# Led.net
KiCad netlist of a schematic drawn in Altium Designer
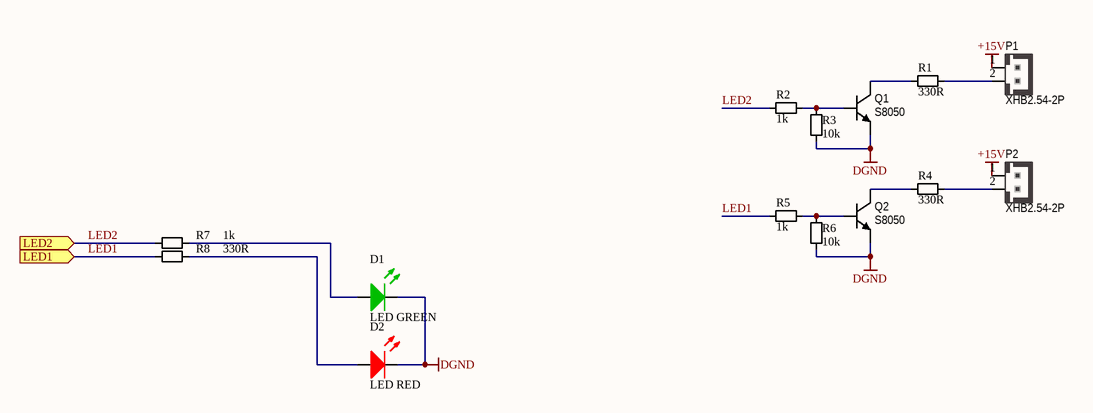
[diagram p0: Led.SchDoc]

(export (version "E")
  (design (tool "Eeschema 10.0.6"))
  (components
    (comp (ref "D1")
      (value "LED GREEN")
      (footprint "GreenBox:0805-LED-G")
      (description "LIGHT EMITTING DIODE 0805 GREEN")
      (fields (field (name "PUBLISHER") "GreenBox"))
      (libsource (lib "Diode_Transistor") (part "D614000000G0"))
    )
    (comp (ref "D2")
      (value "LED RED")
      (footprint "GreenBox:0805-LED-R")
      (description "LIGHT EMITTING DIODE 0805 RED")
      (fields (field (name "PUBLISHER") "GreenBox"))
      (libsource (lib "Diode_Transistor") (part "D614000000R0"))
    )
    (comp (ref "P1")
      (value "XHB2.54-2P")
      (footprint "GreenBox:XH-2")
      (description "Header XHB2.54-2P 2.54mm")
      (fields (field (name "PUBLISHER") "GreenBox"))
      (libsource (lib "Connectors") (part "P6DX02Z25400"))
    )
    (comp (ref "P2")
      (value "XHB2.54-2P")
      (footprint "GreenBox:XH-2")
      (description "Header XHB2.54-2P 2.54mm")
      (fields (field (name "PUBLISHER") "GreenBox"))
      (libsource (lib "Connectors") (part "P6DX02Z25400"))
    )
    (comp (ref "Q1")
      (value "S8050")
      (footprint "GreenBox:SOT-23_N")
      (description "NPN S8050 Icm 0.5A Vcbo 40V")
      (fields (field (name "PUBLISHER") "GreenBox"))
      (libsource (lib "Diode_Transistor") (part "DN42S8050000"))
    )
    (comp (ref "Q2")
      (value "S8050")
      (footprint "GreenBox:SOT-23_N")
      (description "NPN S8050 Icm 0.5A Vcbo 40V")
      (fields (field (name "PUBLISHER") "GreenBox"))
      (libsource (lib "Diode_Transistor") (part "DN42S8050000"))
    )
    (comp (ref "R1")
      (value "330R")
      (footprint "GreenBox:0603-R")
      (description "SMD Resistor 330R 1% 1/10W 0603 100PPM")
      (fields (field (name "Comment") "Res") (field (name "PUBLISHER") "GreenBox"))
      (libsource (lib "Resistor") (part "R11C330RFBF0"))
    )
    (comp (ref "R2")
      (value "1k")
      (footprint "GreenBox:0603-R")
      (description "SMD Resistor 1k 1% 1/10W 0603 100PPM")
      (fields (field (name "Comment") "Res") (field (name "PUBLISHER") "GreenBox"))
      (libsource (lib "Resistor") (part "R11C001KFBF0"))
    )
    (comp (ref "R3")
      (value "10k")
      (footprint "GreenBox:0603-R")
      (description "SMD Resistor 10k 1% 1/10W 0603 100PPM")
      (fields (field (name "Comment") "Res") (field (name "PUBLISHER") "GreenBox"))
      (libsource (lib "Resistor") (part "R11C010KFBF0"))
    )
    (comp (ref "R4")
      (value "330R")
      (footprint "GreenBox:0603-R")
      (description "SMD Resistor 330R 1% 1/10W 0603 100PPM")
      (fields (field (name "Comment") "Res") (field (name "PUBLISHER") "GreenBox"))
      (libsource (lib "Resistor") (part "R11C330RFBF0"))
    )
    (comp (ref "R5")
      (value "1k")
      (footprint "GreenBox:0603-R")
      (description "SMD Resistor 1k 1% 1/10W 0603 100PPM")
      (fields (field (name "Comment") "Res") (field (name "PUBLISHER") "GreenBox"))
      (libsource (lib "Resistor") (part "R11C001KFBF0"))
    )
    (comp (ref "R6")
      (value "10k")
      (footprint "GreenBox:0603-R")
      (description "SMD Resistor 10k 1% 1/10W 0603 100PPM")
      (fields (field (name "Comment") "Res") (field (name "PUBLISHER") "GreenBox"))
      (libsource (lib "Resistor") (part "R11C010KFBF0"))
    )
    (comp (ref "R7")
      (value "1k")
      (footprint "GreenBox:0603-R")
      (description "SMD Resistor 1k 1% 1/10W 0603 100PPM")
      (fields (field (name "Comment") "Res") (field (name "PUBLISHER") "GreenBox"))
      (libsource (lib "Resistor") (part "R11C001KFBF0"))
    )
    (comp (ref "R8")
      (value "330R")
      (footprint "GreenBox:0603-R")
      (description "SMD Resistor 330R 1% 1/10W 0603 100PPM")
      (fields (field (name "Comment") "Res") (field (name "PUBLISHER") "GreenBox"))
      (libsource (lib "Resistor") (part "R11C330RFBF0"))
    )
  )
  (nets
    (net (code "1") (name "+15V") (class "Default")
      (node (ref "P1") (pin "1") (pinfunction "1_1") (pintype "passive"))
      (node (ref "P2") (pin "1") (pinfunction "1_1") (pintype "passive"))
    )
    (net (code "2") (name "/LED1") (class "Default")
      (node (ref "R5") (pin "1") (pinfunction "1_1") (pintype "passive"))
      (node (ref "R8") (pin "1") (pinfunction "1_1") (pintype "passive"))
    )
    (net (code "3") (name "/LED2") (class "Default")
      (node (ref "R2") (pin "1") (pinfunction "1_1") (pintype "passive"))
      (node (ref "R7") (pin "1") (pinfunction "1_1") (pintype "passive"))
    )
    (net (code "4") (name "DGND") (class "Default")
      (node (ref "D1") (pin "2") (pinfunction "2_2") (pintype "passive"))
      (node (ref "D2") (pin "2") (pinfunction "2_2") (pintype "passive"))
      (node (ref "Q1") (pin "2") (pinfunction "E_2") (pintype "passive"))
      (node (ref "Q2") (pin "2") (pinfunction "E_2") (pintype "passive"))
      (node (ref "R3") (pin "2") (pinfunction "2_2") (pintype "passive"))
      (node (ref "R6") (pin "2") (pinfunction "2_2") (pintype "passive"))
    )
    (net (code "5") (name "Net-(D1-Pad1)") (class "Default")
      (node (ref "D1") (pin "1") (pinfunction "1_1") (pintype "passive"))
      (node (ref "R7") (pin "2") (pinfunction "2_2") (pintype "passive"))
    )
    (net (code "6") (name "Net-(D2-Pad1)") (class "Default")
      (node (ref "D2") (pin "1") (pinfunction "1_1") (pintype "passive"))
      (node (ref "R8") (pin "2") (pinfunction "2_2") (pintype "passive"))
    )
    (net (code "7") (name "Net-(P1-Pad2)") (class "Default")
      (node (ref "P1") (pin "2") (pinfunction "2_2") (pintype "passive"))
      (node (ref "R1") (pin "2") (pinfunction "2_2") (pintype "passive"))
    )
    (net (code "8") (name "Net-(P2-Pad2)") (class "Default")
      (node (ref "P2") (pin "2") (pinfunction "2_2") (pintype "passive"))
      (node (ref "R4") (pin "2") (pinfunction "2_2") (pintype "passive"))
    )
    (net (code "9") (name "Net-(Q1-B)") (class "Default")
      (node (ref "Q1") (pin "1") (pinfunction "B_1") (pintype "passive"))
      (node (ref "R2") (pin "2") (pinfunction "2_2") (pintype "passive"))
      (node (ref "R3") (pin "1") (pinfunction "1_1") (pintype "passive"))
    )
    (net (code "10") (name "Net-(Q1-C)") (class "Default")
      (node (ref "Q1") (pin "3") (pinfunction "C_3") (pintype "passive"))
      (node (ref "R1") (pin "1") (pinfunction "1_1") (pintype "passive"))
    )
    (net (code "11") (name "Net-(Q2-B)") (class "Default")
      (node (ref "Q2") (pin "1") (pinfunction "B_1") (pintype "passive"))
      (node (ref "R5") (pin "2") (pinfunction "2_2") (pintype "passive"))
      (node (ref "R6") (pin "1") (pinfunction "1_1") (pintype "passive"))
    )
    (net (code "12") (name "Net-(Q2-C)") (class "Default")
      (node (ref "Q2") (pin "3") (pinfunction "C_3") (pintype "passive"))
      (node (ref "R4") (pin "1") (pinfunction "1_1") (pintype "passive"))
    )
  )
)
